# Charger.net
KiCad netlist of a schematic drawn in Altium Designer
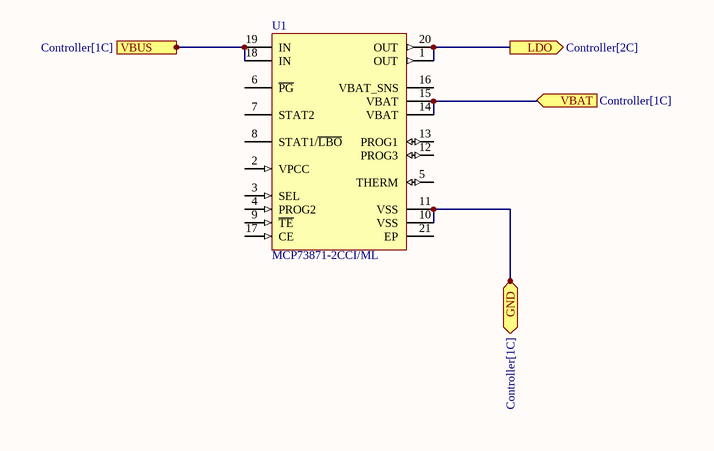
[diagram p0: Charger.SchDoc]

(export (version "E")
  (design (tool "Eeschema 10.0.6"))
  (components
    (comp (ref "U1")
      (value "MCP73871-2CCI/ML")
      (footprint "QFN-ML20_M")
      (libsource (lib "Altium Content Vault") (part "PM-BM-MCP73871-SQ21"))
    )
  )
  (nets
    (net (code "1") (name "/GND") (class "Default")
      (node (ref "U1") (pin "10") (pinfunction "VSS_10") (pintype "power_in"))
      (node (ref "U1") (pin "11") (pinfunction "VSS_11") (pintype "power_in"))
    )
    (net (code "2") (name "/LDO") (class "Default")
      (node (ref "U1") (pin "1") (pinfunction "OUT_1") (pintype "output"))
      (node (ref "U1") (pin "20") (pinfunction "OUT_20") (pintype "output"))
    )
    (net (code "3") (name "/VBAT") (class "Default")
      (node (ref "U1") (pin "14") (pinfunction "VBAT_14") (pintype "power_in"))
      (node (ref "U1") (pin "15") (pinfunction "VBAT_15") (pintype "power_in"))
    )
    (net (code "4") (name "/VBUS") (class "Default")
      (node (ref "U1") (pin "18") (pinfunction "IN_18") (pintype "power_in"))
      (node (ref "U1") (pin "19") (pinfunction "IN_19") (pintype "power_in"))
    )
    (net (code "5") (name "unconnected-(U1-CE-Pad17)") (class "Default")
      (node (ref "U1") (pin "17") (pinfunction "CE_17") (pintype "input"))
    )
    (net (code "6") (name "unconnected-(U1-EP-Pad21)") (class "Default")
      (node (ref "U1") (pin "21") (pinfunction "EP_21") (pintype "power_in"))
    )
    (net (code "7") (name "unconnected-(U1-PROG1-Pad13)") (class "Default")
      (node (ref "U1") (pin "13") (pinfunction "PROG1_13") (pintype "bidirectional"))
    )
    (net (code "8") (name "unconnected-(U1-PROG2-Pad4)") (class "Default")
      (node (ref "U1") (pin "4") (pinfunction "PROG2_4") (pintype "input"))
    )
    (net (code "9") (name "unconnected-(U1-PROG3-Pad12)") (class "Default")
      (node (ref "U1") (pin "12") (pinfunction "PROG3_12") (pintype "bidirectional"))
    )
    (net (code "10") (name "unconnected-(U1-SEL-Pad3)") (class "Default")
      (node (ref "U1") (pin "3") (pinfunction "SEL_3") (pintype "input"))
    )
    (net (code "11") (name "unconnected-(U1-STAT1{slash}~{LBO}-Pad8)") (class "Default")
      (node (ref "U1") (pin "8") (pinfunction "STAT1/~{LBO}_8") (pintype "open_collector"))
    )
    (net (code "12") (name "unconnected-(U1-STAT2-Pad7)") (class "Default")
      (node (ref "U1") (pin "7") (pinfunction "STAT2_7") (pintype "open_collector"))
    )
    (net (code "13") (name "unconnected-(U1-THERM-Pad5)") (class "Default")
      (node (ref "U1") (pin "5") (pinfunction "THERM_5") (pintype "bidirectional"))
    )
    (net (code "14") (name "unconnected-(U1-VBAT_SNS-Pad16)") (class "Default")
      (node (ref "U1") (pin "16") (pinfunction "VBAT_SNS_16") (pintype "power_in"))
    )
    (net (code "15") (name "unconnected-(U1-VPCC-Pad2)") (class "Default")
      (node (ref "U1") (pin "2") (pinfunction "VPCC_2") (pintype "input"))
    )
    (net (code "16") (name "unconnected-(U1-~{PG}-Pad6)") (class "Default")
      (node (ref "U1") (pin "6") (pinfunction "~{PG}_6") (pintype "open_collector"))
    )
    (net (code "17") (name "unconnected-(U1-~{TE}-Pad9)") (class "Default")
      (node (ref "U1") (pin "9") (pinfunction "~{TE}_9") (pintype "input"))
    )
  )
)
